# Arduino-Pro-v17.net
KiCad netlist of a schematic drawn in EAGLE
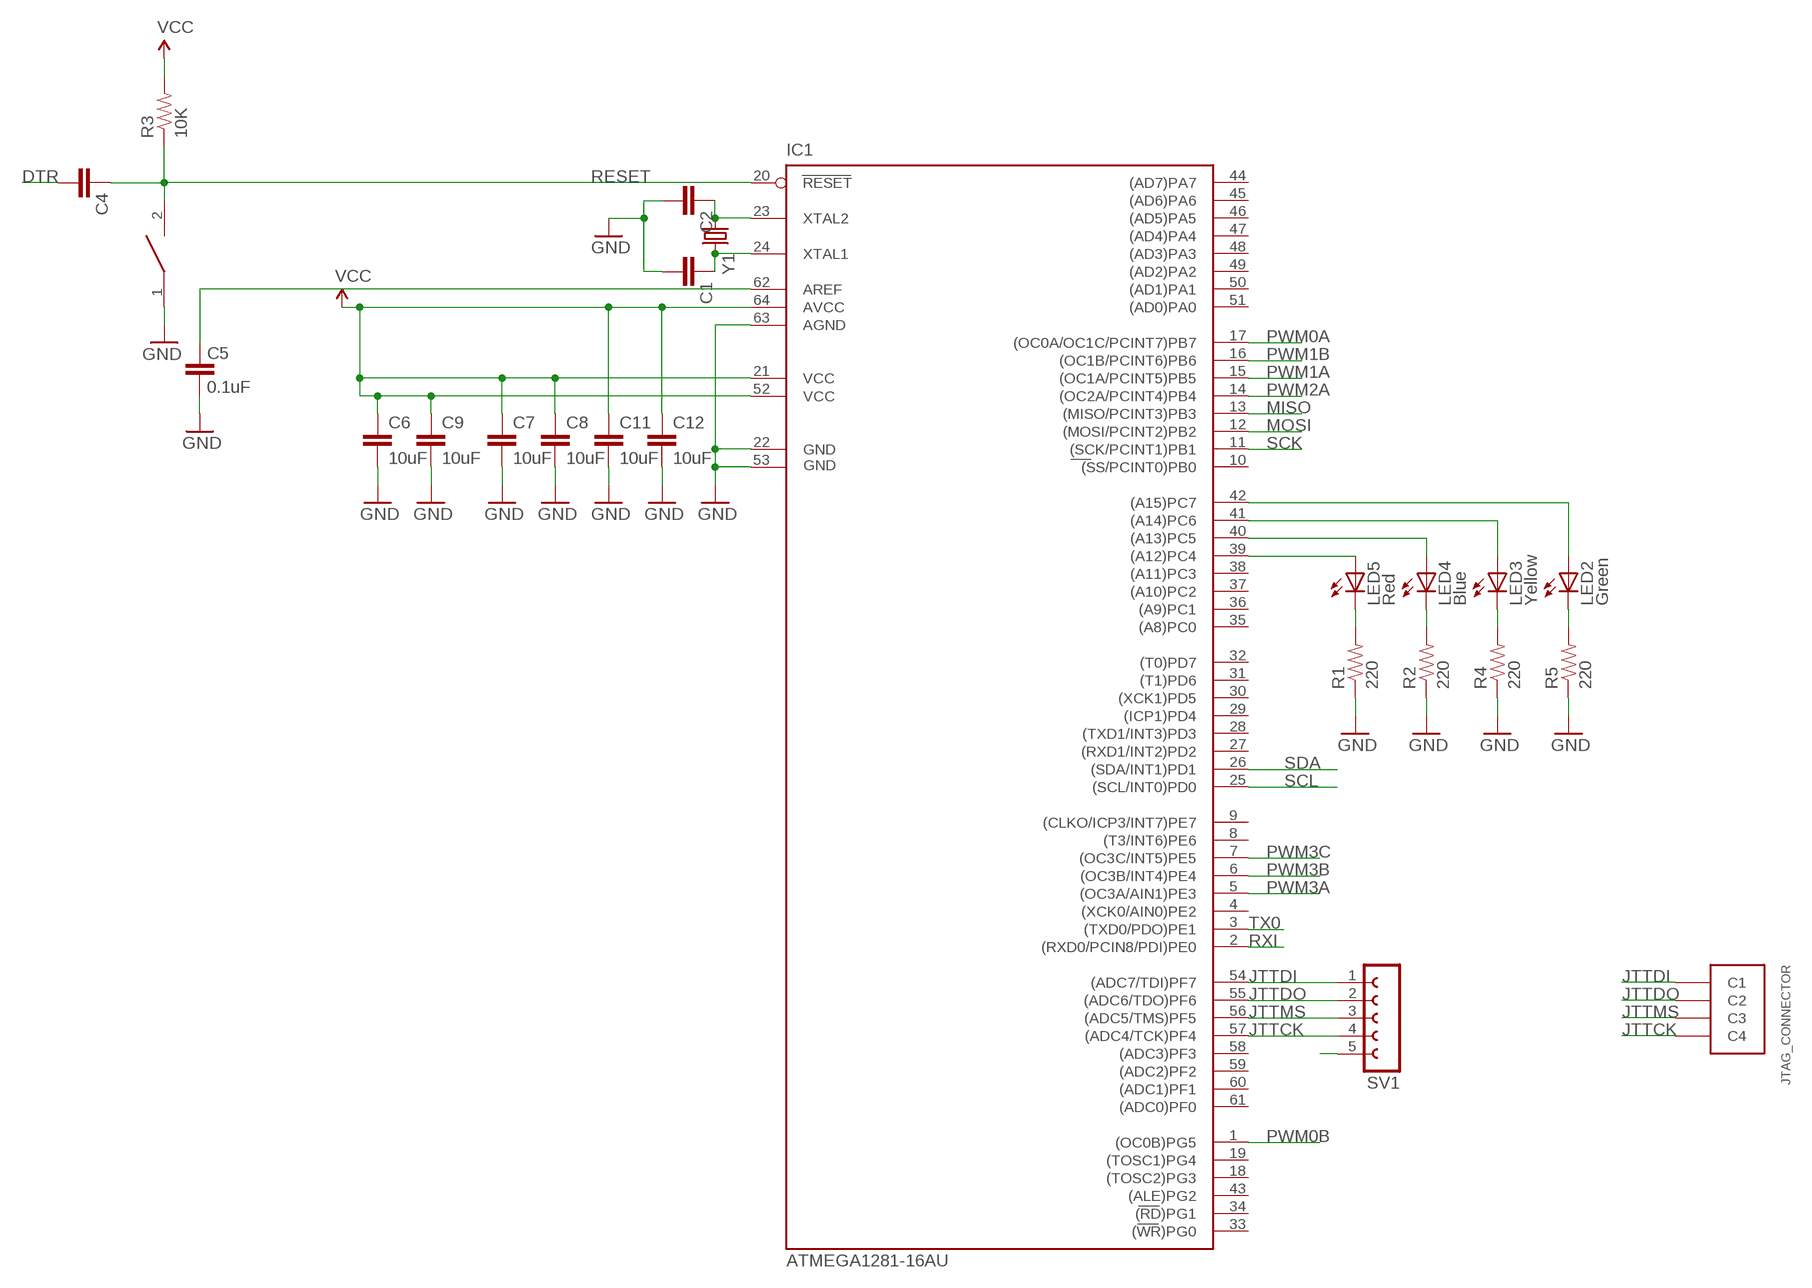
[diagram p0: schematic, sheet 1, part 1 of 2]
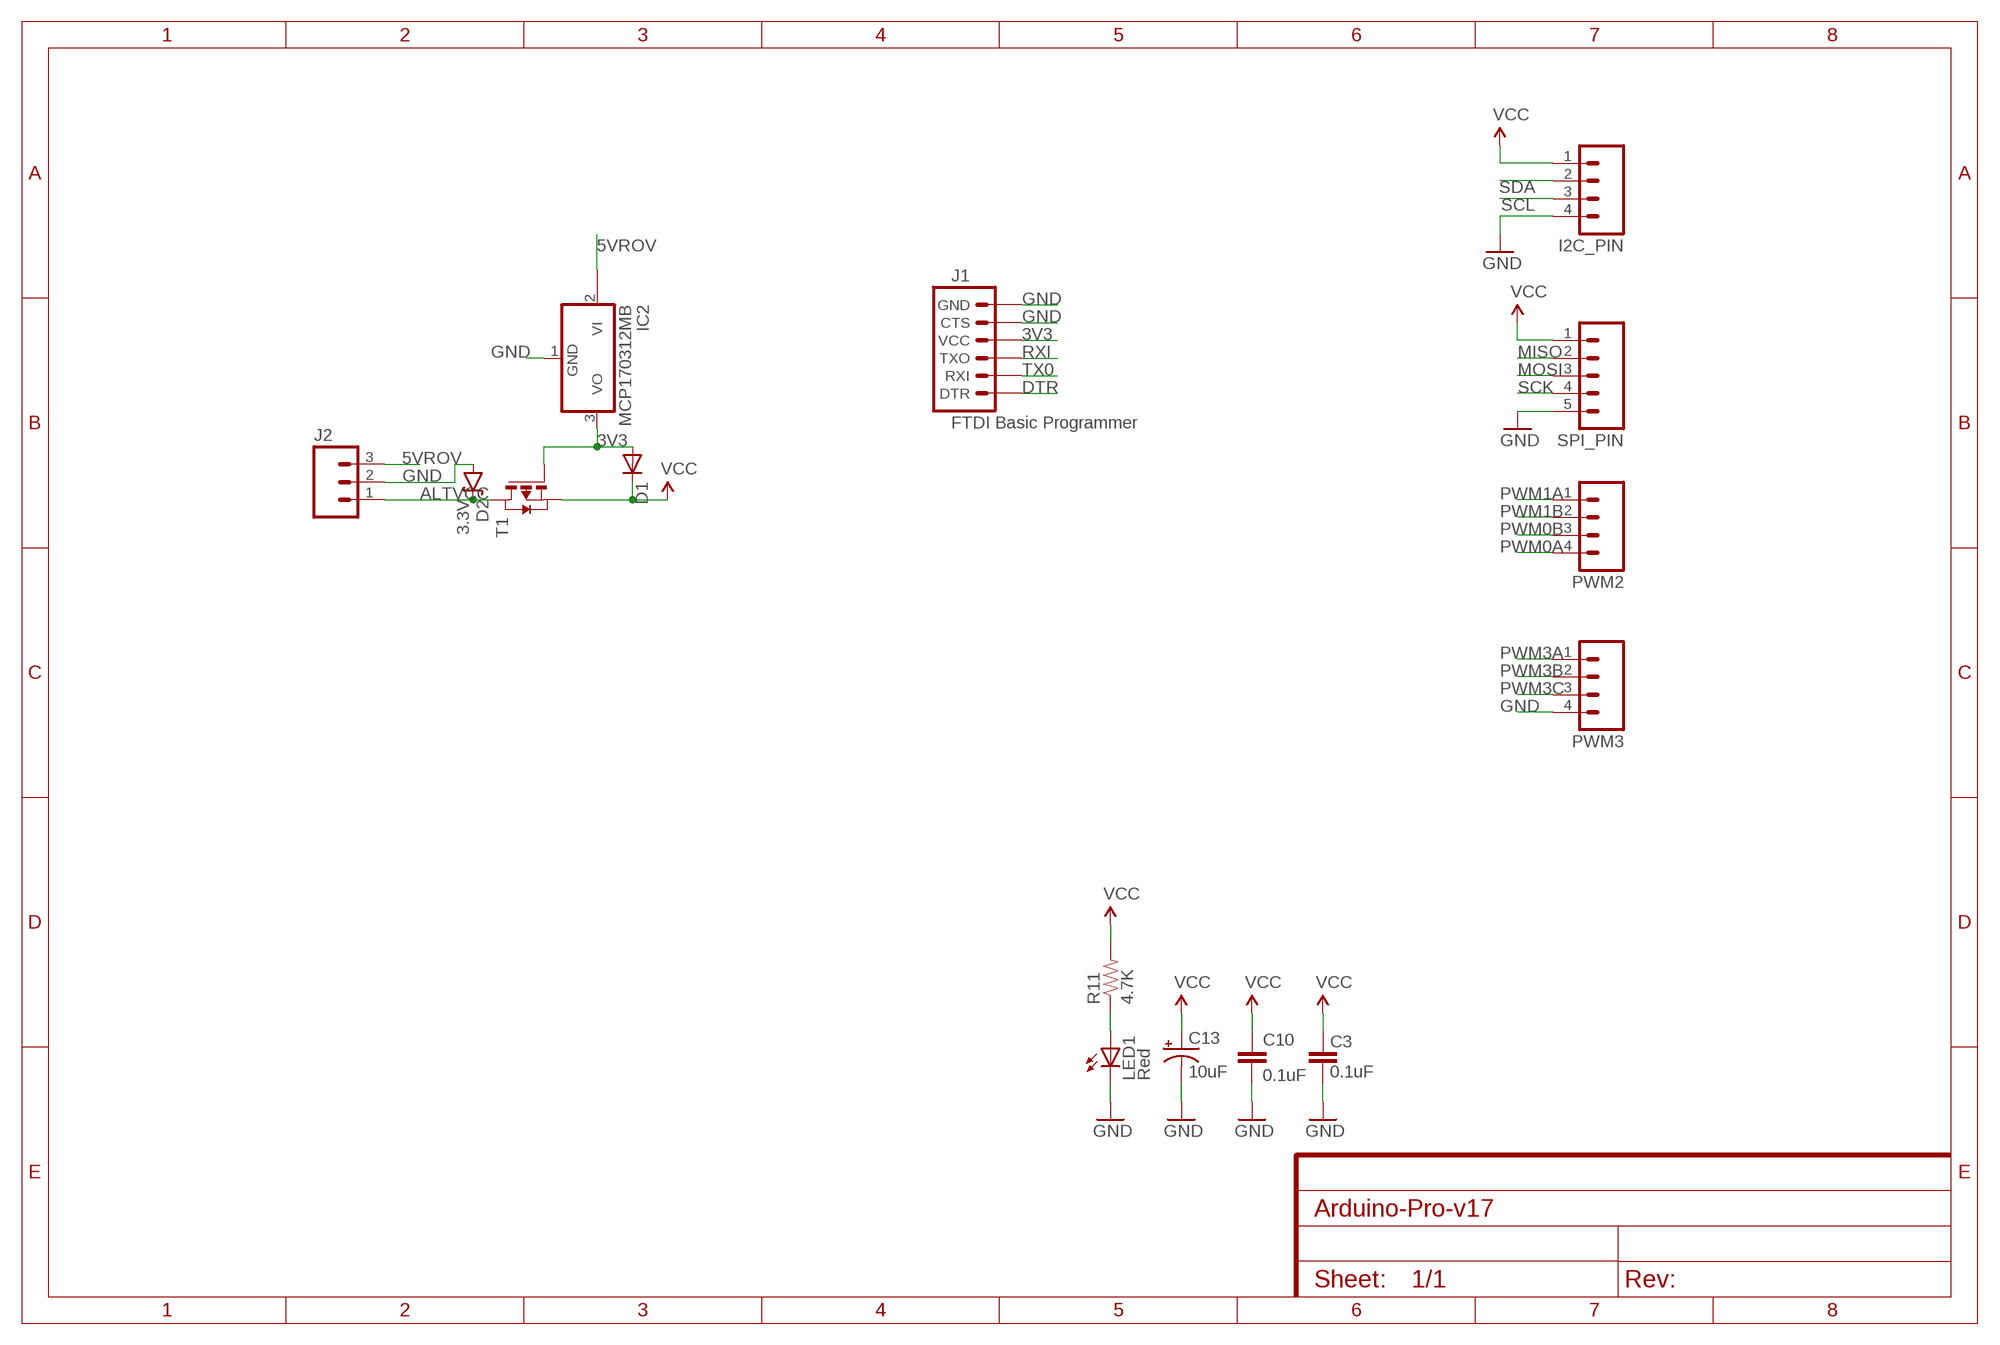
[diagram p1: schematic, sheet 1, part 2 of 2]

(export (version "E")
  (design (tool "Eeschema 10.0.6"))
  (components
    (comp (ref "C1")
      (value "CAP0603-CAP")
      (footprint "eagle-import:0603-CAP")
      (libsource (lib "eagle-import") (part "SparkFun-Capacitors_CAP0603-CAP"))
    )
    (comp (ref "C2")
      (value "CAP0603-CAP")
      (footprint "eagle-import:0603-CAP")
      (libsource (lib "eagle-import") (part "SparkFun-Capacitors_CAP0603-CAP"))
    )
    (comp (ref "C3")
      (value "0.1uF")
      (footprint "eagle-import:0402-CAP")
      (libsource (lib "eagle-import") (part "CAP0402-CAP"))
    )
    (comp (ref "C4")
      (value "CAP0603-CAP")
      (footprint "eagle-import:0603-CAP")
      (libsource (lib "eagle-import") (part "SparkFun-Capacitors_CAP0603-CAP"))
    )
    (comp (ref "C5")
      (value "0.1uF")
      (footprint "eagle-import:0402-CAP")
      (libsource (lib "eagle-import") (part "CAP0402-CAP"))
    )
    (comp (ref "C6")
      (value "10uF")
      (footprint "eagle-import:0603-CAP")
      (libsource (lib "eagle-import") (part "SparkFun-Passives_CAP0603-CAP"))
    )
    (comp (ref "C7")
      (value "10uF")
      (footprint "eagle-import:0603-CAP")
      (libsource (lib "eagle-import") (part "SparkFun-Passives_CAP0603-CAP"))
    )
    (comp (ref "C8")
      (value "10uF")
      (footprint "eagle-import:0603-CAP")
      (libsource (lib "eagle-import") (part "SparkFun-Passives_CAP0603-CAP"))
    )
    (comp (ref "C9")
      (value "10uF")
      (footprint "eagle-import:0603-CAP")
      (libsource (lib "eagle-import") (part "SparkFun-Passives_CAP0603-CAP"))
    )
    (comp (ref "C10")
      (value "0.1uF")
      (footprint "eagle-import:0402-CAP")
      (libsource (lib "eagle-import") (part "CAP0402-CAP"))
    )
    (comp (ref "C11")
      (value "10uF")
      (footprint "eagle-import:0603-CAP")
      (libsource (lib "eagle-import") (part "SparkFun-Passives_CAP0603-CAP"))
    )
    (comp (ref "C12")
      (value "10uF")
      (footprint "eagle-import:0603-CAP")
      (libsource (lib "eagle-import") (part "SparkFun-Passives_CAP0603-CAP"))
    )
    (comp (ref "C13")
      (value "10uF")
      (footprint "eagle-import:EIA3216")
      (libsource (lib "eagle-import") (part "CAP_POL1206"))
    )
    (comp (ref "D1")
      (value "DIODE-DO-214AC")
      (footprint "eagle-import:DO-214AC")
      (libsource (lib "eagle-import") (part "DIODE-DO-214AC"))
    )
    (comp (ref "D2")
      (value "3.3V")
      (footprint "eagle-import:SOD-323")
      (libsource (lib "eagle-import") (part "DIODE-ZENER3.3V"))
    )
    (comp (ref "I2C_PIN")
      (value "M04PTH")
      (footprint "eagle-import:1X04")
      (libsource (lib "eagle-import") (part "M04PTH"))
    )
    (comp (ref "IC1")
      (value "ATMEGA1281-16AU")
      (footprint "eagle-import:TQFP64")
      (libsource (lib "eagle-import") (part "ATMEGA1281AU-16"))
    )
    (comp (ref "IC2")
      (value "MCP170312MB")
      (footprint "eagle-import:SOT89")
      (libsource (lib "eagle-import") (part "MCP1703MB12"))
    )
    (comp (ref "J1")
      (value "FTDI Basic Programmer")
      (footprint "eagle-import:1X06")
      (libsource (lib "eagle-import") (part "ARDUINO_SERIAL_PROGRAMPTH"))
    )
    (comp (ref "J2")
      (value "M03PTH")
      (footprint "eagle-import:1X03")
      (libsource (lib "eagle-import") (part "M03PTH"))
    )
    (comp (ref "JTAG_CONNECTOR")
      (value "MICRO-FIT-4-SMD-PART")
      (footprint "eagle-import:MICRO-FIT-4-SMD")
      (libsource (lib "eagle-import") (part "MICRO-FIT-4-SMD-PART"))
    )
    (comp (ref "LED1")
      (value "Red")
      (footprint "eagle-import:LED-0603")
      (libsource (lib "eagle-import") (part "LED0603"))
    )
    (comp (ref "LED2")
      (value "Green")
      (footprint "eagle-import:LED-0603")
      (libsource (lib "eagle-import") (part "LED0603"))
    )
    (comp (ref "LED3")
      (value "Yellow")
      (footprint "eagle-import:LED-0603")
      (libsource (lib "eagle-import") (part "LED0603"))
    )
    (comp (ref "LED4")
      (value "Blue")
      (footprint "eagle-import:LED-0603")
      (libsource (lib "eagle-import") (part "LED0603"))
    )
    (comp (ref "LED5")
      (value "Red")
      (footprint "eagle-import:LED-0603")
      (libsource (lib "eagle-import") (part "LED0603"))
    )
    (comp (ref "PWM2")
      (value "M04PTH")
      (footprint "eagle-import:1X04")
      (libsource (lib "eagle-import") (part "M04PTH"))
    )
    (comp (ref "PWM3")
      (value "M04PTH")
      (footprint "eagle-import:1X04")
      (libsource (lib "eagle-import") (part "M04PTH"))
    )
    (comp (ref "R1")
      (value "220")
      (footprint "eagle-import:0402-RES")
      (libsource (lib "eagle-import") (part "RESISTOR0402-RES"))
    )
    (comp (ref "R2")
      (value "220")
      (footprint "eagle-import:0402-RES")
      (libsource (lib "eagle-import") (part "RESISTOR0402-RES"))
    )
    (comp (ref "R3")
      (value "10K")
      (footprint "eagle-import:0603-RES")
      (libsource (lib "eagle-import") (part "SparkFun-Passives_RESISTOR0603-RES"))
    )
    (comp (ref "R4")
      (value "220")
      (footprint "eagle-import:0402-RES")
      (libsource (lib "eagle-import") (part "RESISTOR0402-RES"))
    )
    (comp (ref "R5")
      (value "220")
      (footprint "eagle-import:0402-RES")
      (libsource (lib "eagle-import") (part "RESISTOR0402-RES"))
    )
    (comp (ref "R11")
      (value "4.7K")
      (footprint "eagle-import:0402-RES")
      (libsource (lib "eagle-import") (part "RESISTOR0402-RES"))
    )
    (comp (ref "SPI_PIN")
      (value "M05PTH")
      (footprint "eagle-import:1X05")
      (libsource (lib "eagle-import") (part "M05PTH"))
    )
    (comp (ref "SV1")
      (value "FE05-1")
      (footprint "eagle-import:FE05-1")
      (libsource (lib "eagle-import") (part "FE05-1"))
    )
    (comp (ref "T1")
      (value "FDN340P")
      (footprint "eagle-import:SOT-23")
      (libsource (lib "eagle-import") (part "FDN340P"))
    )
    (comp (ref "U$1")
      (value "SWITCH")
      (footprint "eagle-import:SW_2512")
      (libsource (lib "eagle-import") (part "SWITCH"))
    )
    (comp (ref "Y1")
      (value "CRYSTALHC49US")
      (footprint "eagle-import:HC49US")
      (libsource (lib "eagle-import") (part "CRYSTALHC49US"))
    )
  )
  (nets
    (net (code "1") (name "/3V3") (class "Default")
      (node (ref "D1") (pin "A") (pinfunction "A_A") (pintype "passive"))
      (node (ref "IC2") (pin "3") (pinfunction "VO_3") (pintype "passive"))
      (node (ref "J1") (pin "4") (pinfunction "VCC_4") (pintype "passive"))
      (node (ref "T1") (pin "3") (pinfunction "G_3") (pintype "passive"))
    )
    (net (code "2") (name "/5VROV") (class "Default")
      (node (ref "IC2") (pin "2@1") (pinfunction "VI1_2@1") (pintype "input"))
      (node (ref "J2") (pin "3") (pinfunction "3_3") (pintype "passive"))
    )
    (net (code "3") (name "/ALTVCC") (class "Default")
      (node (ref "D2") (pin "C") (pinfunction "C_C") (pintype "passive"))
      (node (ref "J2") (pin "1") (pinfunction "1_1") (pintype "passive"))
      (node (ref "T1") (pin "1") (pinfunction "D_1") (pintype "passive"))
    )
    (net (code "4") (name "/DTR") (class "Default")
      (node (ref "C4") (pin "2") (pinfunction "2_2") (pintype "passive"))
      (node (ref "J1") (pin "1") (pinfunction "DTR_1") (pintype "passive"))
    )
    (net (code "5") (name "/JTTCK") (class "Default")
      (node (ref "IC1") (pin "57") (pinfunction "(ADC4/TCK)PF4_57") (pintype "bidirectional"))
      (node (ref "JTAG_CONNECTOR") (pin "C4") (pinfunction "C4_C4") (pintype "bidirectional"))
      (node (ref "SV1") (pin "4") (pinfunction "4_4") (pintype "passive"))
    )
    (net (code "6") (name "/JTTDI") (class "Default")
      (node (ref "IC1") (pin "54") (pinfunction "(ADC7/TDI)PF7_54") (pintype "bidirectional"))
      (node (ref "JTAG_CONNECTOR") (pin "C1") (pinfunction "C1_C1") (pintype "bidirectional"))
      (node (ref "SV1") (pin "1") (pinfunction "1_1") (pintype "passive"))
    )
    (net (code "7") (name "/JTTDO") (class "Default")
      (node (ref "IC1") (pin "55") (pinfunction "(ADC6/TDO)PF6_55") (pintype "bidirectional"))
      (node (ref "JTAG_CONNECTOR") (pin "C2") (pinfunction "C2_C2") (pintype "bidirectional"))
      (node (ref "SV1") (pin "2") (pinfunction "2_2") (pintype "passive"))
    )
    (net (code "8") (name "/JTTMS") (class "Default")
      (node (ref "IC1") (pin "56") (pinfunction "(ADC5/TMS)PF5_56") (pintype "bidirectional"))
      (node (ref "JTAG_CONNECTOR") (pin "C3") (pinfunction "C3_C3") (pintype "bidirectional"))
      (node (ref "SV1") (pin "3") (pinfunction "3_3") (pintype "passive"))
    )
    (net (code "9") (name "/MISO") (class "Default")
      (node (ref "IC1") (pin "13") (pinfunction "(MISO/PCINT3)PB3_13") (pintype "bidirectional"))
      (node (ref "SPI_PIN") (pin "2") (pinfunction "2_2") (pintype "passive"))
    )
    (net (code "10") (name "/MOSI") (class "Default")
      (node (ref "IC1") (pin "12") (pinfunction "(MOSI/PCINT2)PB2_12") (pintype "bidirectional"))
      (node (ref "SPI_PIN") (pin "3") (pinfunction "3_3") (pintype "passive"))
    )
    (net (code "11") (name "/PWM0A") (class "Default")
      (node (ref "IC1") (pin "17") (pinfunction "(OC0A/OC1C/PCINT7)PB7_17") (pintype "bidirectional"))
      (node (ref "PWM2") (pin "4") (pinfunction "4_4") (pintype "passive"))
    )
    (net (code "12") (name "/PWM0B") (class "Default")
      (node (ref "IC1") (pin "1") (pinfunction "(OC0B)PG5_1") (pintype "bidirectional"))
      (node (ref "PWM2") (pin "3") (pinfunction "3_3") (pintype "passive"))
    )
    (net (code "13") (name "/PWM1A") (class "Default")
      (node (ref "IC1") (pin "15") (pinfunction "(OC1A/PCINT5)PB5_15") (pintype "bidirectional"))
      (node (ref "PWM2") (pin "1") (pinfunction "1_1") (pintype "passive"))
    )
    (net (code "14") (name "/PWM1B") (class "Default")
      (node (ref "IC1") (pin "16") (pinfunction "(OC1B/PCINT6)PB6_16") (pintype "bidirectional"))
      (node (ref "PWM2") (pin "2") (pinfunction "2_2") (pintype "passive"))
    )
    (net (code "15") (name "/PWM2A") (class "Default")
      (node (ref "IC1") (pin "14") (pinfunction "(OC2A/PCINT4)PB4_14") (pintype "bidirectional"))
    )
    (net (code "16") (name "/PWM3A") (class "Default")
      (node (ref "IC1") (pin "5") (pinfunction "(OC3A/AIN1)PE3_5") (pintype "bidirectional"))
      (node (ref "PWM3") (pin "1") (pinfunction "1_1") (pintype "passive"))
    )
    (net (code "17") (name "/PWM3B") (class "Default")
      (node (ref "IC1") (pin "6") (pinfunction "(OC3B/INT4)PE4_6") (pintype "bidirectional"))
      (node (ref "PWM3") (pin "2") (pinfunction "2_2") (pintype "passive"))
    )
    (net (code "18") (name "/PWM3C") (class "Default")
      (node (ref "IC1") (pin "7") (pinfunction "(OC3C/INT5)PE5_7") (pintype "bidirectional"))
      (node (ref "PWM3") (pin "3") (pinfunction "3_3") (pintype "passive"))
    )
    (net (code "19") (name "/RESET") (class "Default")
      (node (ref "C4") (pin "1") (pinfunction "1_1") (pintype "passive"))
      (node (ref "IC1") (pin "20") (pinfunction "RESET_20") (pintype "input"))
      (node (ref "R3") (pin "1") (pinfunction "1_1") (pintype "passive"))
      (node (ref "U$1") (pin "2") (pinfunction "P$2_2") (pintype "bidirectional"))
    )
    (net (code "20") (name "/RXI") (class "Default")
      (node (ref "IC1") (pin "2") (pinfunction "(RXD0/PCIN8/PDI)PE0_2") (pintype "bidirectional"))
      (node (ref "J1") (pin "3") (pinfunction "TXO_3") (pintype "passive"))
    )
    (net (code "21") (name "/SCK") (class "Default")
      (node (ref "IC1") (pin "11") (pinfunction "(SCK/PCINT1)PB1_11") (pintype "bidirectional"))
      (node (ref "SPI_PIN") (pin "4") (pinfunction "4_4") (pintype "passive"))
    )
    (net (code "22") (name "/SCL") (class "Default")
      (node (ref "I2C_PIN") (pin "3") (pinfunction "3_3") (pintype "passive"))
      (node (ref "IC1") (pin "25") (pinfunction "(SCL/INT0)PD0_25") (pintype "bidirectional"))
    )
    (net (code "23") (name "/SDA") (class "Default")
      (node (ref "I2C_PIN") (pin "2") (pinfunction "2_2") (pintype "passive"))
      (node (ref "IC1") (pin "26") (pinfunction "(SDA/INT1)PD1_26") (pintype "bidirectional"))
    )
    (net (code "24") (name "/TX0") (class "Default")
      (node (ref "IC1") (pin "3") (pinfunction "(TXD0/PDO)PE1_3") (pintype "bidirectional"))
      (node (ref "J1") (pin "2") (pinfunction "RXI_2") (pintype "passive"))
    )
    (net (code "25") (name "GND") (class "Default")
      (node (ref "C1") (pin "2") (pinfunction "2_2") (pintype "passive"))
      (node (ref "C10") (pin "2") (pinfunction "2_2") (pintype "passive"))
      (node (ref "C11") (pin "2") (pinfunction "2_2") (pintype "passive"))
      (node (ref "C12") (pin "2") (pinfunction "2_2") (pintype "passive"))
      (node (ref "C13") (pin "C") (pinfunction "-_C") (pintype "passive"))
      (node (ref "C2") (pin "2") (pinfunction "2_2") (pintype "passive"))
      (node (ref "C3") (pin "1") (pinfunction "1_1") (pintype "passive"))
      (node (ref "C5") (pin "1") (pinfunction "1_1") (pintype "passive"))
      (node (ref "C6") (pin "2") (pinfunction "2_2") (pintype "passive"))
      (node (ref "C7") (pin "2") (pinfunction "2_2") (pintype "passive"))
      (node (ref "C8") (pin "2") (pinfunction "2_2") (pintype "passive"))
      (node (ref "C9") (pin "2") (pinfunction "2_2") (pintype "passive"))
      (node (ref "D2") (pin "A") (pinfunction "A_A") (pintype "passive"))
      (node (ref "I2C_PIN") (pin "4") (pinfunction "4_4") (pintype "passive"))
      (node (ref "IC1") (pin "22") (pinfunction "GND_22") (pintype "power_in"))
      (node (ref "IC1") (pin "53") (pinfunction "GND1_53") (pintype "power_in"))
      (node (ref "IC1") (pin "63") (pinfunction "AGND_63") (pintype "power_in"))
      (node (ref "IC2") (pin "1") (pinfunction "GND_1") (pintype "passive"))
      (node (ref "J1") (pin "5") (pinfunction "CTS_5") (pintype "passive"))
      (node (ref "J1") (pin "6") (pinfunction "GND_6") (pintype "passive"))
      (node (ref "J2") (pin "2") (pinfunction "2_2") (pintype "passive"))
      (node (ref "LED1") (pin "C") (pinfunction "C_C") (pintype "passive"))
      (node (ref "PWM3") (pin "4") (pinfunction "4_4") (pintype "passive"))
      (node (ref "R1") (pin "1") (pinfunction "1_1") (pintype "passive"))
      (node (ref "R2") (pin "1") (pinfunction "1_1") (pintype "passive"))
      (node (ref "R4") (pin "1") (pinfunction "1_1") (pintype "passive"))
      (node (ref "R5") (pin "1") (pinfunction "1_1") (pintype "passive"))
      (node (ref "SPI_PIN") (pin "5") (pinfunction "5_5") (pintype "passive"))
      (node (ref "SV1") (pin "5") (pinfunction "5_5") (pintype "passive"))
      (node (ref "U$1") (pin "1") (pinfunction "P$1_1") (pintype "bidirectional"))
    )
    (net (code "26") (name "Net-(IC1-(A12)PC4)") (class "Default")
      (node (ref "IC1") (pin "39") (pinfunction "(A12)PC4_39") (pintype "bidirectional"))
      (node (ref "LED5") (pin "A") (pinfunction "A_A") (pintype "passive"))
    )
    (net (code "27") (name "Net-(IC1-(A13)PC5)") (class "Default")
      (node (ref "IC1") (pin "40") (pinfunction "(A13)PC5_40") (pintype "bidirectional"))
      (node (ref "LED4") (pin "A") (pinfunction "A_A") (pintype "passive"))
    )
    (net (code "28") (name "Net-(IC1-(A14)PC6)") (class "Default")
      (node (ref "IC1") (pin "41") (pinfunction "(A14)PC6_41") (pintype "bidirectional"))
      (node (ref "LED3") (pin "A") (pinfunction "A_A") (pintype "passive"))
    )
    (net (code "29") (name "Net-(IC1-(A15)PC7)") (class "Default")
      (node (ref "IC1") (pin "42") (pinfunction "(A15)PC7_42") (pintype "bidirectional"))
      (node (ref "LED2") (pin "A") (pinfunction "A_A") (pintype "passive"))
    )
    (net (code "30") (name "Net-(IC1-AREF)") (class "Default")
      (node (ref "C5") (pin "2") (pinfunction "2_2") (pintype "passive"))
      (node (ref "IC1") (pin "62") (pinfunction "AREF_62") (pintype "bidirectional"))
    )
    (net (code "31") (name "Net-(IC1-XTAL1)") (class "Default")
      (node (ref "C1") (pin "1") (pinfunction "1_1") (pintype "passive"))
      (node (ref "IC1") (pin "24") (pinfunction "XTAL1_24") (pintype "input"))
      (node (ref "Y1") (pin "2") (pinfunction "2_2") (pintype "passive"))
    )
    (net (code "32") (name "Net-(IC1-XTAL2)") (class "Default")
      (node (ref "C2") (pin "1") (pinfunction "1_1") (pintype "passive"))
      (node (ref "IC1") (pin "23") (pinfunction "XTAL2_23") (pintype "output"))
      (node (ref "Y1") (pin "1") (pinfunction "1_1") (pintype "passive"))
    )
    (net (code "33") (name "Net-(LED1-PadA)") (class "Default")
      (node (ref "LED1") (pin "A") (pinfunction "A_A") (pintype "passive"))
      (node (ref "R11") (pin "1") (pinfunction "1_1") (pintype "passive"))
    )
    (net (code "34") (name "Net-(LED2-PadC)") (class "Default")
      (node (ref "LED2") (pin "C") (pinfunction "C_C") (pintype "passive"))
      (node (ref "R5") (pin "2") (pinfunction "2_2") (pintype "passive"))
    )
    (net (code "35") (name "Net-(LED3-PadC)") (class "Default")
      (node (ref "LED3") (pin "C") (pinfunction "C_C") (pintype "passive"))
      (node (ref "R4") (pin "2") (pinfunction "2_2") (pintype "passive"))
    )
    (net (code "36") (name "Net-(LED4-PadC)") (class "Default")
      (node (ref "LED4") (pin "C") (pinfunction "C_C") (pintype "passive"))
      (node (ref "R2") (pin "2") (pinfunction "2_2") (pintype "passive"))
    )
    (net (code "37") (name "Net-(LED5-PadC)") (class "Default")
      (node (ref "LED5") (pin "C") (pinfunction "C_C") (pintype "passive"))
      (node (ref "R1") (pin "2") (pinfunction "2_2") (pintype "passive"))
    )
    (net (code "38") (name "VCC") (class "Default")
      (node (ref "C10") (pin "1") (pinfunction "1_1") (pintype "passive"))
      (node (ref "C11") (pin "1") (pinfunction "1_1") (pintype "passive"))
      (node (ref "C12") (pin "1") (pinfunction "1_1") (pintype "passive"))
      (node (ref "C13") (pin "A") (pinfunction "+_A") (pintype "passive"))
      (node (ref "C3") (pin "2") (pinfunction "2_2") (pintype "passive"))
      (node (ref "C6") (pin "1") (pinfunction "1_1") (pintype "passive"))
      (node (ref "C7") (pin "1") (pinfunction "1_1") (pintype "passive"))
      (node (ref "C8") (pin "1") (pinfunction "1_1") (pintype "passive"))
      (node (ref "C9") (pin "1") (pinfunction "1_1") (pintype "passive"))
      (node (ref "D1") (pin "C") (pinfunction "C_C") (pintype "passive"))
      (node (ref "I2C_PIN") (pin "1") (pinfunction "1_1") (pintype "passive"))
      (node (ref "IC1") (pin "21") (pinfunction "VCC_21") (pintype "power_in"))
      (node (ref "IC1") (pin "52") (pinfunction "VCC1_52") (pintype "power_in"))
      (node (ref "IC1") (pin "64") (pinfunction "AVCC_64") (pintype "power_in"))
      (node (ref "R11") (pin "2") (pinfunction "2_2") (pintype "passive"))
      (node (ref "R3") (pin "2") (pinfunction "2_2") (pintype "passive"))
      (node (ref "SPI_PIN") (pin "1") (pinfunction "1_1") (pintype "passive"))
      (node (ref "T1") (pin "2") (pinfunction "S_2") (pintype "passive"))
    )
    (net (code "39") (name "unconnected-(IC1-(A8)PC0-Pad35)") (class "Default")
      (node (ref "IC1") (pin "35") (pinfunction "(A8)PC0_35") (pintype "bidirectional"))
    )
    (net (code "40") (name "unconnected-(IC1-(A9)PC1-Pad36)") (class "Default")
      (node (ref "IC1") (pin "36") (pinfunction "(A9)PC1_36") (pintype "bidirectional"))
    )
    (net (code "41") (name "unconnected-(IC1-(A10)PC2-Pad37)") (class "Default")
      (node (ref "IC1") (pin "37") (pinfunction "(A10)PC2_37") (pintype "bidirectional"))
    )
    (net (code "42") (name "unconnected-(IC1-(A11)PC3-Pad38)") (class "Default")
      (node (ref "IC1") (pin "38") (pinfunction "(A11)PC3_38") (pintype "bidirectional"))
    )
    (net (code "43") (name "unconnected-(IC1-(AD0)PA0-Pad51)") (class "Default")
      (node (ref "IC1") (pin "51") (pinfunction "(AD0)PA0_51") (pintype "bidirectional"))
    )
    (net (code "44") (name "unconnected-(IC1-(AD1)PA1-Pad50)") (class "Default")
      (node (ref "IC1") (pin "50") (pinfunction "(AD1)PA1_50") (pintype "bidirectional"))
    )
    (net (code "45") (name "unconnected-(IC1-(AD2)PA2-Pad49)") (class "Default")
      (node (ref "IC1") (pin "49") (pinfunction "(AD2)PA2_49") (pintype "bidirectional"))
    )
    (net (code "46") (name "unconnected-(IC1-(AD3)PA3-Pad48)") (class "Default")
      (node (ref "IC1") (pin "48") (pinfunction "(AD3)PA3_48") (pintype "bidirectional"))
    )
    (net (code "47") (name "unconnected-(IC1-(AD4)PA4-Pad47)") (class "Default")
      (node (ref "IC1") (pin "47") (pinfunction "(AD4)PA4_47") (pintype "bidirectional"))
    )
    (net (code "48") (name "unconnected-(IC1-(AD5)PA5-Pad46)") (class "Default")
      (node (ref "IC1") (pin "46") (pinfunction "(AD5)PA5_46") (pintype "bidirectional"))
    )
    (net (code "49") (name "unconnected-(IC1-(AD6)PA6-Pad45)") (class "Default")
      (node (ref "IC1") (pin "45") (pinfunction "(AD6)PA6_45") (pintype "bidirectional"))
    )
    (net (code "50") (name "unconnected-(IC1-(AD7)PA7-Pad44)") (class "Default")
      (node (ref "IC1") (pin "44") (pinfunction "(AD7)PA7_44") (pintype "bidirectional"))
    )
    (net (code "51") (name "unconnected-(IC1-(ADC0)PF0-Pad61)") (class "Default")
      (node (ref "IC1") (pin "61") (pinfunction "(ADC0)PF0_61") (pintype "bidirectional"))
    )
    (net (code "52") (name "unconnected-(IC1-(ADC1)PF1-Pad60)") (class "Default")
      (node (ref "IC1") (pin "60") (pinfunction "(ADC1)PF1_60") (pintype "bidirectional"))
    )
    (net (code "53") (name "unconnected-(IC1-(ADC2)PF2-Pad59)") (class "Default")
      (node (ref "IC1") (pin "59") (pinfunction "(ADC2)PF2_59") (pintype "bidirectional"))
    )
    (net (code "54") (name "unconnected-(IC1-(ADC3)PF3-Pad58)") (class "Default")
      (node (ref "IC1") (pin "58") (pinfunction "(ADC3)PF3_58") (pintype "bidirectional"))
    )
    (net (code "55") (name "unconnected-(IC1-(ALE)PG2-Pad43)") (class "Default")
      (node (ref "IC1") (pin "43") (pinfunction "(ALE)PG2_43") (pintype "bidirectional"))
    )
    (net (code "56") (name "unconnected-(IC1-(CLKO{slash}ICP3{slash}INT7)PE7-Pad9)") (class "Default")
      (node (ref "IC1") (pin "9") (pinfunction "(CLKO/ICP3/INT7)PE7_9") (pintype "bidirectional"))
    )
    (net (code "57") (name "unconnected-(IC1-(ICP1)PD4-Pad29)") (class "Default")
      (node (ref "IC1") (pin "29") (pinfunction "(ICP1)PD4_29") (pintype "bidirectional"))
    )
    (net (code "58") (name "unconnected-(IC1-(RD)PG1-Pad34)") (class "Default")
      (node (ref "IC1") (pin "34") (pinfunction "(RD)PG1_34") (pintype "bidirectional"))
    )
    (net (code "59") (name "unconnected-(IC1-(RXD1{slash}INT2)PD2-Pad27)") (class "Default")
      (node (ref "IC1") (pin "27") (pinfunction "(RXD1/INT2)PD2_27") (pintype "bidirectional"))
    )
    (net (code "60") (name "unconnected-(IC1-(SS{slash}PCINT0)PB0-Pad10)") (class "Default")
      (node (ref "IC1") (pin "10") (pinfunction "(SS/PCINT0)PB0_10") (pintype "bidirectional"))
    )
    (net (code "61") (name "unconnected-(IC1-(T0)PD7-Pad32)") (class "Default")
      (node (ref "IC1") (pin "32") (pinfunction "(T0)PD7_32") (pintype "bidirectional"))
    )
    (net (code "62") (name "unconnected-(IC1-(T1)PD6-Pad31)") (class "Default")
      (node (ref "IC1") (pin "31") (pinfunction "(T1)PD6_31") (pintype "bidirectional"))
    )
    (net (code "63") (name "unconnected-(IC1-(T3{slash}INT6)PE6-Pad8)") (class "Default")
      (node (ref "IC1") (pin "8") (pinfunction "(T3/INT6)PE6_8") (pintype "bidirectional"))
    )
    (net (code "64") (name "unconnected-(IC1-(TOSC1)PG4-Pad19)") (class "Default")
      (node (ref "IC1") (pin "19") (pinfunction "(TOSC1)PG4_19") (pintype "bidirectional"))
    )
    (net (code "65") (name "unconnected-(IC1-(TOSC2)PG3-Pad18)") (class "Default")
      (node (ref "IC1") (pin "18") (pinfunction "(TOSC2)PG3_18") (pintype "bidirectional"))
    )
    (net (code "66") (name "unconnected-(IC1-(TXD1{slash}INT3)PD3-Pad28)") (class "Default")
      (node (ref "IC1") (pin "28") (pinfunction "(TXD1/INT3)PD3_28") (pintype "bidirectional"))
    )
    (net (code "67") (name "unconnected-(IC1-(WR)PG0-Pad33)") (class "Default")
      (node (ref "IC1") (pin "33") (pinfunction "(WR)PG0_33") (pintype "bidirectional"))
    )
    (net (code "68") (name "unconnected-(IC1-(XCK0{slash}AIN0)PE2-Pad4)") (class "Default")
      (node (ref "IC1") (pin "4") (pinfunction "(XCK0/AIN0)PE2_4") (pintype "bidirectional"))
    )
    (net (code "69") (name "unconnected-(IC1-(XCK1)PD5-Pad30)") (class "Default")
      (node (ref "IC1") (pin "30") (pinfunction "(XCK1)PD5_30") (pintype "bidirectional"))
    )
    (net (code "70") (name "unconnected-(IC2-VI-Pad2)") (class "Default")
      (node (ref "IC2") (pin "2") (pinfunction "VI_2") (pintype "input"))
    )
  )
)
